# 06_Power.net
KiCad netlist of a schematic drawn in Altium Designer
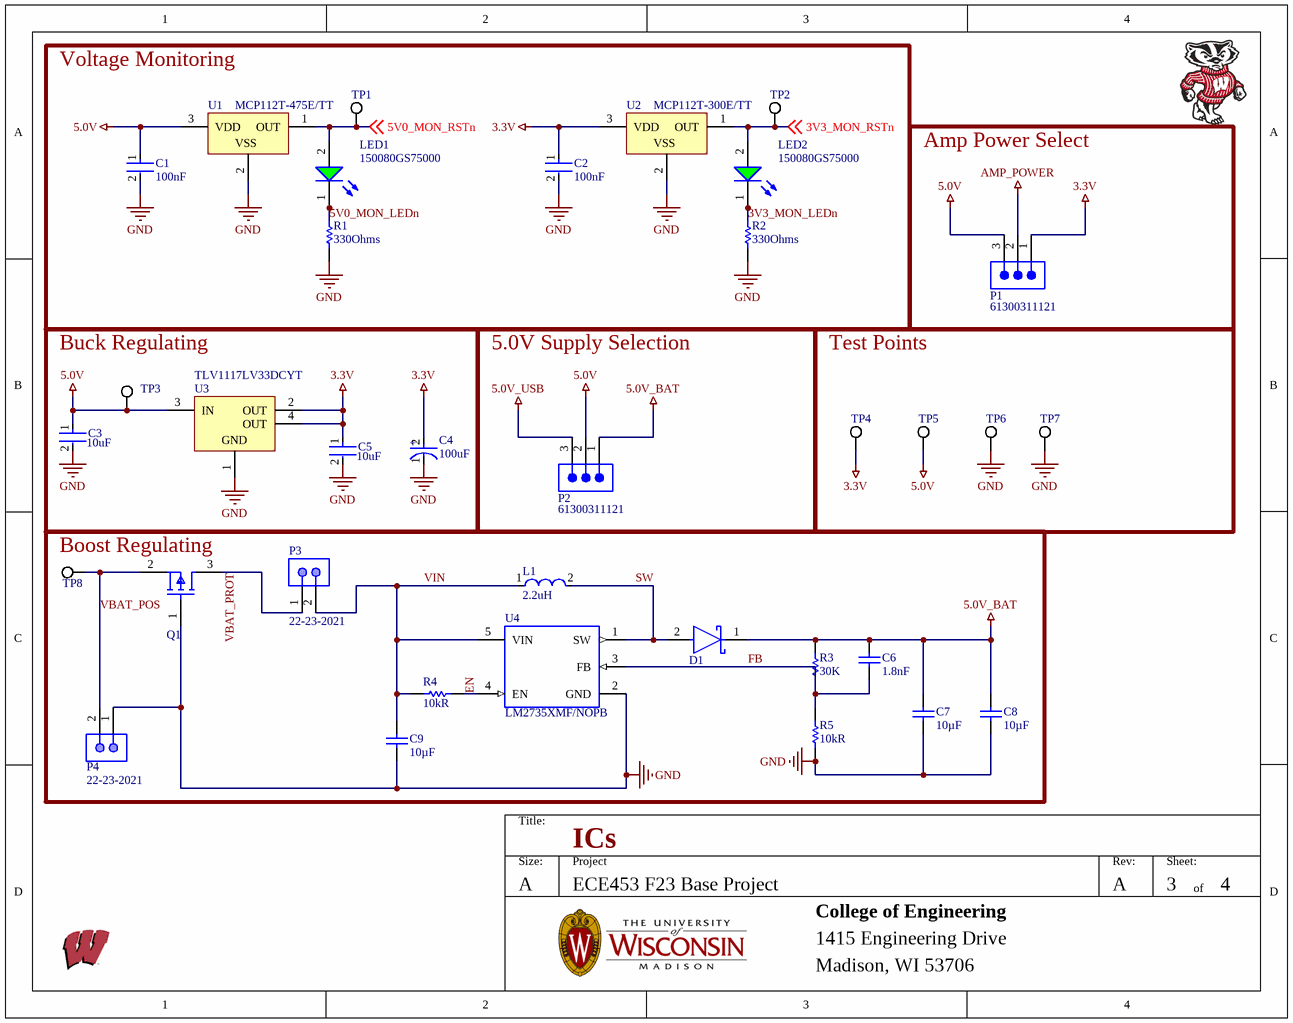
[diagram p0: 06_Power.SchDoc]

(export (version "E")
  (design (tool "Eeschema 10.0.6"))
  (components
    (comp (ref "C1")
      (value "100nF")
      (footprint "FP-C0805C-DN-MFG")
      (description "CAP CER 0.1UF 50V X7R 0805")
      (fields
        (field (name "MANUFACTURER") "KEMET")
        (field (name "MANUFACTURER PART NUMBER") "C0805C104K5RACTU")
      )
      (libsource (lib "ECE453") (part "CMP-2007-00279-2"))
    )
    (comp (ref "C2")
      (value "100nF")
      (footprint "FP-C0805C-DN-MFG")
      (description "CAP CER 0.1UF 50V X7R 0805")
      (fields
        (field (name "MANUFACTURER") "KEMET")
        (field (name "MANUFACTURER PART NUMBER") "C0805C104K5RACTU")
      )
      (libsource (lib "ECE453") (part "CMP-2007-00279-2"))
    )
    (comp (ref "C3")
      (value "10uF")
      (footprint "FP-C0805C-DG-MFG")
      (description "CAP CER 10UF 10V X5R 0805")
      (fields
        (field (name "MANUFACTURER") "Kemet")
        (field (name "MANUFACTURER PART NUMBER") "C0805C106K8PACTU")
      )
      (libsource (lib "Altium Content Vault") (part "11868f565c42a9108669ba33697ecf6"))
    )
    (comp (ref "C4")
      (value "EEE-1EA101XP")
      (footprint "FP-SD8-MFG")
      (description "CAP ALUM 100UF 20% 25V SMD")
      (fields
        (field (name "CAPACITANCE") "100uF")
        (field (name "VOLTAGE") "25V")
        (field (name "TOLERANCE") "20%")
      )
      (libsource (lib "Altium Content Vault") (part "a00bbbee19879c290e62620ae7e47b1"))
    )
    (comp (ref "C5")
      (value "10uF")
      (footprint "FP-C0805C-DG-MFG")
      (description "CAP CER 10UF 10V X5R 0805")
      (fields
        (field (name "MANUFACTURER") "Kemet")
        (field (name "MANUFACTURER PART NUMBER") "C0805C106K8PACTU")
      )
      (libsource (lib "Altium Content Vault") (part "11868f565c42a9108669ba33697ecf6"))
    )
    (comp (ref "C6")
      (value "CAP_0805_N_001_80")
      (footprint "CAP_0805")
      (fields
        (field (name "TOLERANCE") "5%")
        (field (name "VOLTAGE") "50V")
        (field (name "CAPACITANCE") "1.8nF")
      )
      (libsource (lib "ECE453") (part "CAP_0805_N_001_80"))
    )
    (comp (ref "C7")
      (value "10µF")
      (footprint "CAP_0805")
      (description "CAP CER 10UF 10V X5R 0805")
      (fields
        (field (name "MANUFACTURER") "Samsung Electro-Mechanics America, Inc.")
        (field (name "MANUFACTURER PART NUMBER") "CL21A106KPCLQNC")
      )
      (libsource (lib "ECE453") (part "CAP_0805_U_010_00"))
    )
    (comp (ref "C8")
      (value "10µF")
      (footprint "CAP_0805")
      (description "CAP CER 10UF 10V X5R 0805")
      (fields
        (field (name "MANUFACTURER") "Samsung Electro-Mechanics America, Inc.")
        (field (name "MANUFACTURER PART NUMBER") "CL21A106KPCLQNC")
      )
      (libsource (lib "ECE453") (part "CAP_0805_U_010_00"))
    )
    (comp (ref "C9")
      (value "10µF")
      (footprint "CAP_0805")
      (description "CAP CER 10UF 10V X5R 0805")
      (fields
        (field (name "MANUFACTURER") "Samsung Electro-Mechanics America, Inc.")
        (field (name "MANUFACTURER PART NUMBER") "CL21A106KPCLQNC")
      )
      (libsource (lib "ECE453") (part "CAP_0805_U_010_00"))
    )
    (comp (ref "D1")
      (value "SM5817PL-TP")
      (footprint "On_Semiconductor_425-04_IPC_A")
      (description "DIODE SCHOTTKY 20V 1A SOD123FL")
      (libsource (lib "ECE453") (part "SM5817PL-TP"))
    )
    (comp (ref "L1")
      (value "NRS4018T2R2MDGJ")
      (footprint "IND_TAIYO_NRS4018_TAY")
      (description "Inductor Power Shielded Wirewound 2.2uH 20% 100KHz Ferrite 2.2A 0.0504Ohm DCR 1515 T/R")
      (fields (field (name "TOLERANCE") "20%") (field (name "INDUCTANCE") "2.2uH"))
      (libsource (lib "ECE453") (part "NRS4018T2R2MDGJ"))
    )
    (comp (ref "LED1")
      (value "150080GS75000")
      (footprint "WL-SMCW_0805_150080xx75000")
      (libsource (lib "Altium Content Vault") (part "LED_Green_2A-1K"))
    )
    (comp (ref "LED2")
      (value "150080GS75000")
      (footprint "WL-SMCW_0805_150080xx75000")
      (libsource (lib "Altium Content Vault") (part "LED_Green_2A-1K"))
    )
    (comp (ref "P1")
      (value "61300311121")
      (footprint "61300311121")
      (libsource (lib "Altium Content Vault") (part "Header_Male_1R_03P"))
    )
    (comp (ref "P2")
      (value "61300311121")
      (footprint "61300311121")
      (libsource (lib "Altium Content Vault") (part "Header_Male_1R_03P"))
    )
    (comp (ref "P3")
      (value "22-23-2021")
      (footprint "MOLX-22-23-2021_V")
      (libsource (lib "Altium Content Vault") (part "CN-1P-M-R2"))
    )
    (comp (ref "P4")
      (value "22-23-2021")
      (footprint "MOLX-22-23-2021_V")
      (fields (field (name "MANUFACTURER") "Molex"))
      (libsource (lib "") (part "CN-1P-M-R2_1"))
    )
    (comp (ref "Q1")
      (value "SSM3J328R,LF")
      (footprint "SOT-23_M")
      (description "MOSFET P-CH 20V 6A SOT23F")
      (libsource (lib "ECE453") (part "SSM3J328R,LF"))
    )
    (comp (ref "R1")
      (value "RC0805FR-07330RL")
      (footprint "RESC2013X60X35LL10T20")
      (description "Chip Resistor, 330 Ohm, +/- 1%, 125 mW, -55 to 155 degC, 0805 (2012 Metric), RoHS, Tape and Reel")
      (fields
        (field (name "MANUFACTURER") "Yageo")
        (field (name "TOLERANCE") "1%")
        (field (name "RESISTANCE") "330Ohms")
      )
      (libsource (lib "Altium Content Vault") (part "RES-2"))
    )
    (comp (ref "R2")
      (value "RC0805FR-07330RL")
      (footprint "RESC2013X60X35LL10T20")
      (description "Chip Resistor, 330 Ohm, +/- 1%, 125 mW, -55 to 155 degC, 0805 (2012 Metric), RoHS, Tape and Reel")
      (fields
        (field (name "MANUFACTURER") "Yageo")
        (field (name "TOLERANCE") "1%")
        (field (name "RESISTANCE") "330Ohms")
      )
      (libsource (lib "Altium Content Vault") (part "RES-2"))
    )
    (comp (ref "R3")
      (value "30K")
      (footprint "RES_0805")
      (description "Res Thick Film 0805 30K Ohm 1% 0.125W(1/8W) ±100ppm/°C Pad SMD Automotive T/R")
      (fields (field (name "TOLERANCE") "1%") (field (name "RESISTANCE") "30K"))
      (libsource (lib "ECE453") (part "RES_0805_K_030.00"))
    )
    (comp (ref "R4")
      (value "RES_0805_K_010.00")
      (footprint "RES_0805")
      (description "RES SMD 10K OHM 1% 1/8W 0805")
      (fields (field (name "TOLERANCE") "1%") (field (name "RESISTANCE") "10kR"))
      (libsource (lib "ECE453") (part "RES_0805_K_010.00"))
    )
    (comp (ref "R5")
      (value "RES_0805_K_010.00")
      (footprint "RES_0805")
      (description "RES SMD 10K OHM 1% 1/8W 0805")
      (fields (field (name "TOLERANCE") "1%") (field (name "RESISTANCE") "10kR"))
      (libsource (lib "ECE453") (part "RES_0805_K_010.00"))
    )
    (comp (ref "TP1")
      (value "5019")
      (footprint "KSTN-5019_V")
      (description "Test Point, 1 Position SMD, RoHS, Tape and Reel")
      (libsource (lib "Altium Content Vault") (part "TESTPOINT_WHITE"))
    )
    (comp (ref "TP2")
      (value "5019")
      (footprint "KSTN-5019_V")
      (description "Test Point, 1 Position SMD, RoHS, Tape and Reel")
      (libsource (lib "Altium Content Vault") (part "TESTPOINT_WHITE"))
    )
    (comp (ref "TP3")
      (value "5019")
      (footprint "KSTN-5019_V")
      (description "Test Point, 1 Position SMD, RoHS, Tape and Reel")
      (libsource (lib "Altium Content Vault") (part "TESTPOINT_WHITE"))
    )
    (comp (ref "TP4")
      (value "5019")
      (footprint "KSTN-5019_V")
      (description "Test Point, 1 Position SMD, RoHS, Tape and Reel")
      (libsource (lib "Altium Content Vault") (part "TESTPOINT_WHITE"))
    )
    (comp (ref "TP5")
      (value "5019")
      (footprint "KSTN-5019_V")
      (description "Test Point, 1 Position SMD, RoHS, Tape and Reel")
      (libsource (lib "Altium Content Vault") (part "TESTPOINT_WHITE"))
    )
    (comp (ref "TP6")
      (value "5019")
      (footprint "KSTN-5019_V")
      (description "Test Point, 1 Position SMD, RoHS, Tape and Reel")
      (libsource (lib "Altium Content Vault") (part "TESTPOINT_WHITE"))
    )
    (comp (ref "TP7")
      (value "5019")
      (footprint "KSTN-5019_V")
      (description "Test Point, 1 Position SMD, RoHS, Tape and Reel")
      (libsource (lib "Altium Content Vault") (part "TESTPOINT_WHITE"))
    )
    (comp (ref "TP8")
      (value "5019")
      (footprint "KSTN-5019_V")
      (description "Test Point, 1 Position SMD, RoHS, Tape and Reel")
      (libsource (lib "Altium Content Vault") (part "TESTPOINT_WHITE"))
    )
    (comp (ref "U1")
      (value "MCP112T-475E/TT")
      (footprint "SOT-23-TT3_L")
      (libsource (lib "Altium Content Vault") (part "PM-VLTD-MCP11X-SOT3"))
    )
    (comp (ref "U2")
      (value "MCP112T-300E/TT")
      (footprint "SOT-23-TT3_L")
      (libsource (lib "Altium Content Vault") (part "PM-VLTD-MCP11X-SOT3"))
    )
    (comp (ref "U3")
      (value "TLV1117LV33DCYT")
      (footprint "DCY0004A_M")
      (fields (field (name "MANUFACTURER") "Texas Instruments"))
      (libsource (lib "Altium Content Vault") (part "TI-TLV1117LV33DCY4"))
    )
    (comp (ref "U4")
      (value "LM2735XMF-NOPB")
      (footprint "Texas_Instruments_DBV0005A_0")
      (description "IC REG MULT CONFG ADJ 2.1A SOT23")
      (fields (field (name "MANUFACTURER PART NUMBER 1") "LM2735XMF/NOPB"))
      (libsource (lib "ECE453") (part "LM2735XMF-NOPB"))
    )
  )
  (nets
    (net (code "1") (name "/3V3_MON_LEDn") (class "Default")
      (node (ref "LED2") (pin "1") (pinfunction "K_1") (pintype "passive"))
      (node (ref "R2") (pin "2") (pinfunction "2_2") (pintype "passive"))
    )
    (net (code "2") (name "/5V0_MON_LEDn") (class "Default")
      (node (ref "LED1") (pin "1") (pinfunction "K_1") (pintype "passive"))
      (node (ref "R1") (pin "2") (pinfunction "2_2") (pintype "passive"))
    )
    (net (code "3") (name "/EN") (class "Default")
      (node (ref "R4") (pin "1") (pinfunction "1_1") (pintype "passive"))
      (node (ref "U4") (pin "4") (pinfunction "EN_4") (pintype "input"))
    )
    (net (code "4") (name "/FB") (class "Default")
      (node (ref "C6") (pin "1") (pinfunction "1_1") (pintype "passive"))
      (node (ref "R3") (pin "1") (pinfunction "1_1") (pintype "passive"))
      (node (ref "R5") (pin "2") (pinfunction "2_2") (pintype "passive"))
      (node (ref "U4") (pin "3") (pinfunction "FB_3") (pintype "input"))
    )
    (net (code "5") (name "/SW") (class "Default")
      (node (ref "D1") (pin "2") (pinfunction "A_2") (pintype "passive"))
      (node (ref "L1") (pin "2") (pinfunction "2_2") (pintype "passive"))
      (node (ref "U4") (pin "1") (pinfunction "SW_1") (pintype "output"))
    )
    (net (code "6") (name "/VBAT_POS") (class "Default")
      (node (ref "P4") (pin "2") (pinfunction "2_2") (pintype "passive"))
      (node (ref "Q1") (pin "2") (pinfunction "Source_2") (pintype "passive"))
      (node (ref "TP8") (pin "1") (pinfunction "1_1") (pintype "passive"))
    )
    (net (code "7") (name "/VBAT_PROT") (class "Default")
      (node (ref "P3") (pin "1") (pinfunction "1_1") (pintype "passive"))
      (node (ref "Q1") (pin "3") (pinfunction "Drain_3") (pintype "passive"))
    )
    (net (code "8") (name "/VIN") (class "Default")
      (node (ref "C9") (pin "2") (pinfunction "2_2") (pintype "passive"))
      (node (ref "L1") (pin "1") (pinfunction "1_1") (pintype "passive"))
      (node (ref "P3") (pin "2") (pinfunction "2_2") (pintype "passive"))
      (node (ref "R4") (pin "2") (pinfunction "2_2") (pintype "passive"))
      (node (ref "U4") (pin "5") (pinfunction "VIN_5") (pintype "power_in"))
    )
    (net (code "9") (name "3.3V") (class "Default")
      (node (ref "C2") (pin "1") (pinfunction "1_1") (pintype "passive"))
      (node (ref "C4") (pin "2") (pinfunction "A_2") (pintype "passive"))
      (node (ref "C5") (pin "1") (pinfunction "1_1") (pintype "passive"))
      (node (ref "P1") (pin "1") (pinfunction "1_1") (pintype "passive"))
      (node (ref "TP4") (pin "1") (pinfunction "1_1") (pintype "passive"))
      (node (ref "U2") (pin "3") (pinfunction "VDD_3") (pintype "power_in"))
      (node (ref "U3") (pin "2") (pinfunction "OUT_2") (pintype "power_in"))
      (node (ref "U3") (pin "4") (pinfunction "OUT_4") (pintype "power_in"))
    )
    (net (code "10") (name "3V3_MON_RSTn") (class "Default")
      (node (ref "LED2") (pin "2") (pinfunction "A_2") (pintype "passive"))
      (node (ref "TP2") (pin "1") (pinfunction "1_1") (pintype "passive"))
      (node (ref "U2") (pin "1") (pinfunction "OUT_1") (pintype "power_in"))
    )
    (net (code "11") (name "5.0V") (class "Default")
      (node (ref "C1") (pin "1") (pinfunction "1_1") (pintype "passive"))
      (node (ref "C3") (pin "1") (pinfunction "1_1") (pintype "passive"))
      (node (ref "P1") (pin "3") (pinfunction "3_3") (pintype "passive"))
      (node (ref "P2") (pin "2") (pinfunction "2_2") (pintype "passive"))
      (node (ref "TP3") (pin "1") (pinfunction "1_1") (pintype "passive"))
      (node (ref "TP5") (pin "1") (pinfunction "1_1") (pintype "passive"))
      (node (ref "U1") (pin "3") (pinfunction "VDD_3") (pintype "power_in"))
      (node (ref "U3") (pin "3") (pinfunction "IN_3") (pintype "power_in"))
    )
    (net (code "12") (name "5.0V_BAT") (class "Default")
      (node (ref "C6") (pin "2") (pinfunction "2_2") (pintype "passive"))
      (node (ref "C7") (pin "2") (pinfunction "2_2") (pintype "passive"))
      (node (ref "C8") (pin "2") (pinfunction "2_2") (pintype "passive"))
      (node (ref "D1") (pin "1") (pinfunction "C_1") (pintype "passive"))
      (node (ref "P2") (pin "1") (pinfunction "1_1") (pintype "passive"))
      (node (ref "R3") (pin "2") (pinfunction "2_2") (pintype "passive"))
    )
    (net (code "13") (name "5.0V_USB") (class "Default")
      (node (ref "P2") (pin "3") (pinfunction "3_3") (pintype "passive"))
    )
    (net (code "14") (name "5V0_MON_RSTn") (class "Default")
      (node (ref "LED1") (pin "2") (pinfunction "A_2") (pintype "passive"))
      (node (ref "TP1") (pin "1") (pinfunction "1_1") (pintype "passive"))
      (node (ref "U1") (pin "1") (pinfunction "OUT_1") (pintype "power_in"))
    )
    (net (code "15") (name "AMP_POWER") (class "Default")
      (node (ref "P1") (pin "2") (pinfunction "2_2") (pintype "passive"))
    )
    (net (code "16") (name "GND") (class "Default")
      (node (ref "C1") (pin "2") (pinfunction "2_2") (pintype "passive"))
      (node (ref "C2") (pin "2") (pinfunction "2_2") (pintype "passive"))
      (node (ref "C3") (pin "2") (pinfunction "2_2") (pintype "passive"))
      (node (ref "C4") (pin "1") (pinfunction "C_1") (pintype "passive"))
      (node (ref "C5") (pin "2") (pinfunction "2_2") (pintype "passive"))
      (node (ref "C7") (pin "1") (pinfunction "1_1") (pintype "passive"))
      (node (ref "C8") (pin "1") (pinfunction "1_1") (pintype "passive"))
      (node (ref "C9") (pin "1") (pinfunction "1_1") (pintype "passive"))
      (node (ref "P4") (pin "1") (pinfunction "1_1") (pintype "passive"))
      (node (ref "Q1") (pin "1") (pinfunction "Gate_1") (pintype "passive"))
      (node (ref "R1") (pin "1") (pinfunction "1_1") (pintype "passive"))
      (node (ref "R2") (pin "1") (pinfunction "1_1") (pintype "passive"))
      (node (ref "R5") (pin "1") (pinfunction "1_1") (pintype "passive"))
      (node (ref "TP6") (pin "1") (pinfunction "1_1") (pintype "passive"))
      (node (ref "TP7") (pin "1") (pinfunction "1_1") (pintype "passive"))
      (node (ref "U1") (pin "2") (pinfunction "VSS_2") (pintype "power_in"))
      (node (ref "U2") (pin "2") (pinfunction "VSS_2") (pintype "power_in"))
      (node (ref "U3") (pin "1") (pinfunction "GND_1") (pintype "power_in"))
      (node (ref "U4") (pin "2") (pinfunction "GND_2") (pintype "power_in"))
    )
  )
)
